# STM32_FYP_DAC_Module.net
KiCad netlist of a schematic drawn in Altium Designer
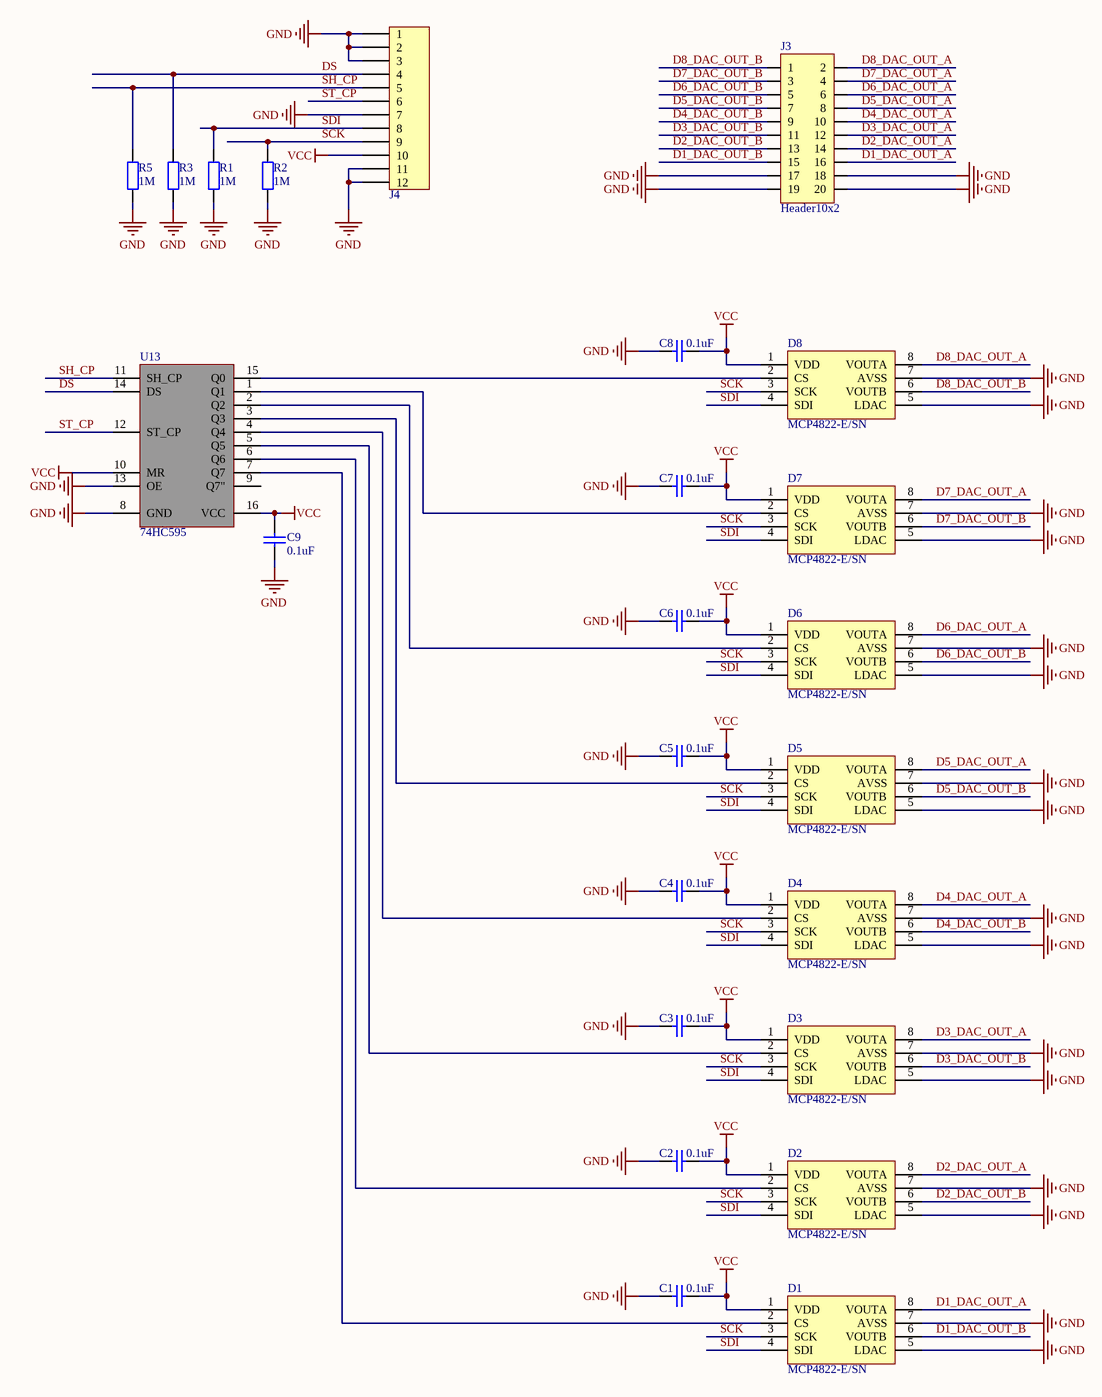
[diagram p0: STM32_FYP_DAC_Module.SchDoc]

(export (version "E")
  (design (tool "Eeschema 10.0.6"))
  (components
    (comp (ref "C1")
      (value "0.1uF")
      (footprint "0805C_M")
      (description "无极性电容")
      (fields (field (name "PUBLISHER") "Altium Limited"))
      (libsource (lib "USER") (part "Cap"))
    )
    (comp (ref "C2")
      (value "0.1uF")
      (footprint "0805C_M")
      (description "无极性电容")
      (fields (field (name "PUBLISHER") "Altium Limited"))
      (libsource (lib "USER") (part "Cap"))
    )
    (comp (ref "C3")
      (value "0.1uF")
      (footprint "0805C_M")
      (description "无极性电容")
      (fields (field (name "PUBLISHER") "Altium Limited"))
      (libsource (lib "USER") (part "Cap"))
    )
    (comp (ref "C4")
      (value "0.1uF")
      (footprint "0805C_M")
      (description "无极性电容")
      (fields (field (name "PUBLISHER") "Altium Limited"))
      (libsource (lib "USER") (part "Cap"))
    )
    (comp (ref "C5")
      (value "0.1uF")
      (footprint "0805C_M")
      (description "无极性电容")
      (fields (field (name "PUBLISHER") "Altium Limited"))
      (libsource (lib "USER") (part "Cap"))
    )
    (comp (ref "C6")
      (value "0.1uF")
      (footprint "0805C_M")
      (description "无极性电容")
      (fields (field (name "PUBLISHER") "Altium Limited"))
      (libsource (lib "USER") (part "Cap"))
    )
    (comp (ref "C7")
      (value "0.1uF")
      (footprint "0805C_M")
      (description "无极性电容")
      (fields (field (name "PUBLISHER") "Altium Limited"))
      (libsource (lib "USER") (part "Cap"))
    )
    (comp (ref "C8")
      (value "0.1uF")
      (footprint "0805C_M")
      (description "无极性电容")
      (fields (field (name "PUBLISHER") "Altium Limited"))
      (libsource (lib "USER") (part "Cap"))
    )
    (comp (ref "C9")
      (value "0.1uF")
      (footprint "0805C_M")
      (description "无极性电容")
      (fields (field (name "PUBLISHER") "Altium Limited"))
      (libsource (lib "USER") (part "Cap"))
    )
    (comp (ref "D1")
      (value "MCP4822-E/SN")
      (footprint "user1:SOIC-8_150mil")
      (description "DAC数模转换芯片")
      (libsource (lib "GUEST") (part "MCP4822"))
    )
    (comp (ref "D2")
      (value "MCP4822-E/SN")
      (footprint "user1:SOIC-8_150mil")
      (description "DAC数模转换芯片")
      (libsource (lib "GUEST") (part "MCP4822"))
    )
    (comp (ref "D3")
      (value "MCP4822-E/SN")
      (footprint "user1:SOIC-8_150mil")
      (description "DAC数模转换芯片")
      (libsource (lib "GUEST") (part "MCP4822"))
    )
    (comp (ref "D4")
      (value "MCP4822-E/SN")
      (footprint "user1:SOIC-8_150mil")
      (description "DAC数模转换芯片")
      (libsource (lib "GUEST") (part "MCP4822"))
    )
    (comp (ref "D5")
      (value "MCP4822-E/SN")
      (footprint "user1:SOIC-8_150mil")
      (description "DAC数模转换芯片")
      (libsource (lib "GUEST") (part "MCP4822"))
    )
    (comp (ref "D6")
      (value "MCP4822-E/SN")
      (footprint "user1:SOIC-8_150mil")
      (description "DAC数模转换芯片")
      (libsource (lib "GUEST") (part "MCP4822"))
    )
    (comp (ref "D7")
      (value "MCP4822-E/SN")
      (footprint "user1:SOIC-8_150mil")
      (description "DAC数模转换芯片")
      (libsource (lib "GUEST") (part "MCP4822"))
    )
    (comp (ref "D8")
      (value "MCP4822-E/SN")
      (footprint "user1:SOIC-8_150mil")
      (description "DAC数模转换芯片")
      (libsource (lib "GUEST") (part "MCP4822"))
    )
    (comp (ref "J3")
      (value "Header10x2")
      (footprint "USER:10PX2-2.54 - H")
      (libsource (lib "USER") (part "Header10x2"))
    )
    (comp (ref "J4")
      (value "Header12")
      (footprint "USER:12P-2.54-H")
      (description "12PIN插座")
      (libsource (lib "USER") (part "Header12"))
    )
    (comp (ref "R1")
      (value "1M")
      (footprint "0805R_M")
      (description "电阻")
      (fields (field (name "PUBLISHER") "Altium Limited"))
      (libsource (lib "USER") (part "Res"))
    )
    (comp (ref "R2")
      (value "1M")
      (footprint "0805R_M")
      (description "电阻")
      (fields (field (name "PUBLISHER") "Altium Limited"))
      (libsource (lib "USER") (part "Res"))
    )
    (comp (ref "R3")
      (value "1M")
      (footprint "0805R_M")
      (description "电阻")
      (fields (field (name "PUBLISHER") "Altium Limited"))
      (libsource (lib "USER") (part "Res"))
    )
    (comp (ref "R5")
      (value "1M")
      (footprint "0805R_M")
      (description "电阻")
      (fields (field (name "PUBLISHER") "Altium Limited"))
      (libsource (lib "USER") (part "Res"))
    )
    (comp (ref "U13")
      (value "74HC595")
      (footprint "user1:SOIC-16_150mil")
      (description "移位寄存器")
      (libsource (lib "GUEST") (part "74LS595"))
    )
  )
  (nets
    (net (code "1") (name "/D1_DAC_OUT_A") (class "Default")
      (node (ref "D1") (pin "8") (pinfunction "VOUTA_8") (pintype "passive"))
      (node (ref "J3") (pin "16") (pinfunction "16_16") (pintype "passive"))
    )
    (net (code "2") (name "/D1_DAC_OUT_B") (class "Default")
      (node (ref "D1") (pin "6") (pinfunction "VOUTB_6") (pintype "passive"))
      (node (ref "J3") (pin "15") (pinfunction "15_15") (pintype "passive"))
    )
    (net (code "3") (name "/D2_DAC_OUT_A") (class "Default")
      (node (ref "D2") (pin "8") (pinfunction "VOUTA_8") (pintype "passive"))
      (node (ref "J3") (pin "14") (pinfunction "14_14") (pintype "passive"))
    )
    (net (code "4") (name "/D2_DAC_OUT_B") (class "Default")
      (node (ref "D2") (pin "6") (pinfunction "VOUTB_6") (pintype "passive"))
      (node (ref "J3") (pin "13") (pinfunction "13_13") (pintype "passive"))
    )
    (net (code "5") (name "/D3_DAC_OUT_A") (class "Default")
      (node (ref "D3") (pin "8") (pinfunction "VOUTA_8") (pintype "passive"))
      (node (ref "J3") (pin "12") (pinfunction "12_12") (pintype "passive"))
    )
    (net (code "6") (name "/D3_DAC_OUT_B") (class "Default")
      (node (ref "D3") (pin "6") (pinfunction "VOUTB_6") (pintype "passive"))
      (node (ref "J3") (pin "11") (pinfunction "11_11") (pintype "passive"))
    )
    (net (code "7") (name "/D4_DAC_OUT_A") (class "Default")
      (node (ref "D4") (pin "8") (pinfunction "VOUTA_8") (pintype "passive"))
      (node (ref "J3") (pin "10") (pinfunction "10_10") (pintype "passive"))
    )
    (net (code "8") (name "/D4_DAC_OUT_B") (class "Default")
      (node (ref "D4") (pin "6") (pinfunction "VOUTB_6") (pintype "passive"))
      (node (ref "J3") (pin "9") (pinfunction "9_9") (pintype "passive"))
    )
    (net (code "9") (name "/D5_DAC_OUT_A") (class "Default")
      (node (ref "D5") (pin "8") (pinfunction "VOUTA_8") (pintype "passive"))
      (node (ref "J3") (pin "8") (pinfunction "8_8") (pintype "passive"))
    )
    (net (code "10") (name "/D5_DAC_OUT_B") (class "Default")
      (node (ref "D5") (pin "6") (pinfunction "VOUTB_6") (pintype "passive"))
      (node (ref "J3") (pin "7") (pinfunction "7_7") (pintype "passive"))
    )
    (net (code "11") (name "/D6_DAC_OUT_A") (class "Default")
      (node (ref "D6") (pin "8") (pinfunction "VOUTA_8") (pintype "passive"))
      (node (ref "J3") (pin "6") (pinfunction "6_6") (pintype "passive"))
    )
    (net (code "12") (name "/D6_DAC_OUT_B") (class "Default")
      (node (ref "D6") (pin "6") (pinfunction "VOUTB_6") (pintype "passive"))
      (node (ref "J3") (pin "5") (pinfunction "5_5") (pintype "passive"))
    )
    (net (code "13") (name "/D7_DAC_OUT_A") (class "Default")
      (node (ref "D7") (pin "8") (pinfunction "VOUTA_8") (pintype "passive"))
      (node (ref "J3") (pin "4") (pinfunction "4_4") (pintype "passive"))
    )
    (net (code "14") (name "/D7_DAC_OUT_B") (class "Default")
      (node (ref "D7") (pin "6") (pinfunction "VOUTB_6") (pintype "passive"))
      (node (ref "J3") (pin "3") (pinfunction "3_3") (pintype "passive"))
    )
    (net (code "15") (name "/D8_DAC_OUT_A") (class "Default")
      (node (ref "D8") (pin "8") (pinfunction "VOUTA_8") (pintype "passive"))
      (node (ref "J3") (pin "2") (pinfunction "2_2") (pintype "passive"))
    )
    (net (code "16") (name "/D8_DAC_OUT_B") (class "Default")
      (node (ref "D8") (pin "6") (pinfunction "VOUTB_6") (pintype "passive"))
      (node (ref "J3") (pin "1") (pinfunction "1_1") (pintype "passive"))
    )
    (net (code "17") (name "/DS") (class "Default")
      (node (ref "J4") (pin "4") (pinfunction "4_4") (pintype "passive"))
      (node (ref "R3") (pin "2") (pinfunction "2_2") (pintype "passive"))
      (node (ref "U13") (pin "14") (pinfunction "DS_14") (pintype "passive"))
    )
    (net (code "18") (name "/SCK") (class "Default")
      (node (ref "D1") (pin "3") (pinfunction "SCK_3") (pintype "passive"))
      (node (ref "D2") (pin "3") (pinfunction "SCK_3") (pintype "passive"))
      (node (ref "D3") (pin "3") (pinfunction "SCK_3") (pintype "passive"))
      (node (ref "D4") (pin "3") (pinfunction "SCK_3") (pintype "passive"))
      (node (ref "D5") (pin "3") (pinfunction "SCK_3") (pintype "passive"))
      (node (ref "D6") (pin "3") (pinfunction "SCK_3") (pintype "passive"))
      (node (ref "D7") (pin "3") (pinfunction "SCK_3") (pintype "passive"))
      (node (ref "D8") (pin "3") (pinfunction "SCK_3") (pintype "passive"))
      (node (ref "J4") (pin "9") (pinfunction "9_9") (pintype "passive"))
      (node (ref "R2") (pin "2") (pinfunction "2_2") (pintype "passive"))
    )
    (net (code "19") (name "/SDI") (class "Default")
      (node (ref "D1") (pin "4") (pinfunction "SDI_4") (pintype "passive"))
      (node (ref "D2") (pin "4") (pinfunction "SDI_4") (pintype "passive"))
      (node (ref "D3") (pin "4") (pinfunction "SDI_4") (pintype "passive"))
      (node (ref "D4") (pin "4") (pinfunction "SDI_4") (pintype "passive"))
      (node (ref "D5") (pin "4") (pinfunction "SDI_4") (pintype "passive"))
      (node (ref "D6") (pin "4") (pinfunction "SDI_4") (pintype "passive"))
      (node (ref "D7") (pin "4") (pinfunction "SDI_4") (pintype "passive"))
      (node (ref "D8") (pin "4") (pinfunction "SDI_4") (pintype "passive"))
      (node (ref "J4") (pin "8") (pinfunction "8_8") (pintype "passive"))
      (node (ref "R1") (pin "2") (pinfunction "2_2") (pintype "passive"))
    )
    (net (code "20") (name "/SH_CP") (class "Default")
      (node (ref "J4") (pin "5") (pinfunction "5_5") (pintype "passive"))
      (node (ref "R5") (pin "2") (pinfunction "2_2") (pintype "passive"))
      (node (ref "U13") (pin "11") (pinfunction "SH_CP_11") (pintype "passive"))
    )
    (net (code "21") (name "/ST_CP") (class "Default")
      (node (ref "J4") (pin "6") (pinfunction "6_6") (pintype "passive"))
      (node (ref "U13") (pin "12") (pinfunction "ST_CP_12") (pintype "passive"))
    )
    (net (code "22") (name "GND") (class "Default")
      (node (ref "C1") (pin "1") (pinfunction "1_1") (pintype "passive"))
      (node (ref "C2") (pin "1") (pinfunction "1_1") (pintype "passive"))
      (node (ref "C3") (pin "1") (pinfunction "1_1") (pintype "passive"))
      (node (ref "C4") (pin "1") (pinfunction "1_1") (pintype "passive"))
      (node (ref "C5") (pin "1") (pinfunction "1_1") (pintype "passive"))
      (node (ref "C6") (pin "1") (pinfunction "1_1") (pintype "passive"))
      (node (ref "C7") (pin "1") (pinfunction "1_1") (pintype "passive"))
      (node (ref "C8") (pin "1") (pinfunction "1_1") (pintype "passive"))
      (node (ref "C9") (pin "1") (pinfunction "1_1") (pintype "passive"))
      (node (ref "D1") (pin "5") (pinfunction "LDAC_5") (pintype "passive"))
      (node (ref "D1") (pin "7") (pinfunction "AVSS_7") (pintype "passive"))
      (node (ref "D2") (pin "5") (pinfunction "LDAC_5") (pintype "passive"))
      (node (ref "D2") (pin "7") (pinfunction "AVSS_7") (pintype "passive"))
      (node (ref "D3") (pin "5") (pinfunction "LDAC_5") (pintype "passive"))
      (node (ref "D3") (pin "7") (pinfunction "AVSS_7") (pintype "passive"))
      (node (ref "D4") (pin "5") (pinfunction "LDAC_5") (pintype "passive"))
      (node (ref "D4") (pin "7") (pinfunction "AVSS_7") (pintype "passive"))
      (node (ref "D5") (pin "5") (pinfunction "LDAC_5") (pintype "passive"))
      (node (ref "D5") (pin "7") (pinfunction "AVSS_7") (pintype "passive"))
      (node (ref "D6") (pin "5") (pinfunction "LDAC_5") (pintype "passive"))
      (node (ref "D6") (pin "7") (pinfunction "AVSS_7") (pintype "passive"))
      (node (ref "D7") (pin "5") (pinfunction "LDAC_5") (pintype "passive"))
      (node (ref "D7") (pin "7") (pinfunction "AVSS_7") (pintype "passive"))
      (node (ref "D8") (pin "5") (pinfunction "LDAC_5") (pintype "passive"))
      (node (ref "D8") (pin "7") (pinfunction "AVSS_7") (pintype "passive"))
      (node (ref "J3") (pin "17") (pinfunction "17_17") (pintype "passive"))
      (node (ref "J3") (pin "18") (pinfunction "18_18") (pintype "passive"))
      (node (ref "J3") (pin "19") (pinfunction "19_19") (pintype "passive"))
      (node (ref "J3") (pin "20") (pinfunction "20_20") (pintype "passive"))
      (node (ref "J4") (pin "1") (pinfunction "1_1") (pintype "passive"))
      (node (ref "J4") (pin "11") (pinfunction "11_11") (pintype "passive"))
      (node (ref "J4") (pin "12") (pinfunction "12_12") (pintype "passive"))
      (node (ref "J4") (pin "2") (pinfunction "2_2") (pintype "passive"))
      (node (ref "J4") (pin "3") (pinfunction "3_3") (pintype "passive"))
      (node (ref "J4") (pin "7") (pinfunction "7_7") (pintype "passive"))
      (node (ref "R1") (pin "1") (pinfunction "1_1") (pintype "passive"))
      (node (ref "R2") (pin "1") (pinfunction "1_1") (pintype "passive"))
      (node (ref "R3") (pin "1") (pinfunction "1_1") (pintype "passive"))
      (node (ref "R5") (pin "1") (pinfunction "1_1") (pintype "passive"))
      (node (ref "U13") (pin "13") (pinfunction "OE_13") (pintype "passive"))
      (node (ref "U13") (pin "8") (pinfunction "GND_8") (pintype "passive"))
    )
    (net (code "23") (name "Net-(D1-CS)") (class "Default")
      (node (ref "D1") (pin "2") (pinfunction "CS_2") (pintype "passive"))
      (node (ref "U13") (pin "7") (pinfunction "Q7_7") (pintype "passive"))
    )
    (net (code "24") (name "Net-(D2-CS)") (class "Default")
      (node (ref "D2") (pin "2") (pinfunction "CS_2") (pintype "passive"))
      (node (ref "U13") (pin "6") (pinfunction "Q6_6") (pintype "passive"))
    )
    (net (code "25") (name "Net-(D3-CS)") (class "Default")
      (node (ref "D3") (pin "2") (pinfunction "CS_2") (pintype "passive"))
      (node (ref "U13") (pin "5") (pinfunction "Q5_5") (pintype "passive"))
    )
    (net (code "26") (name "Net-(D4-CS)") (class "Default")
      (node (ref "D4") (pin "2") (pinfunction "CS_2") (pintype "passive"))
      (node (ref "U13") (pin "4") (pinfunction "Q4_4") (pintype "passive"))
    )
    (net (code "27") (name "Net-(D5-CS)") (class "Default")
      (node (ref "D5") (pin "2") (pinfunction "CS_2") (pintype "passive"))
      (node (ref "U13") (pin "3") (pinfunction "Q3_3") (pintype "passive"))
    )
    (net (code "28") (name "Net-(D6-CS)") (class "Default")
      (node (ref "D6") (pin "2") (pinfunction "CS_2") (pintype "passive"))
      (node (ref "U13") (pin "2") (pinfunction "Q2_2") (pintype "passive"))
    )
    (net (code "29") (name "Net-(D7-CS)") (class "Default")
      (node (ref "D7") (pin "2") (pinfunction "CS_2") (pintype "passive"))
      (node (ref "U13") (pin "1") (pinfunction "Q1_1") (pintype "passive"))
    )
    (net (code "30") (name "Net-(D8-CS)") (class "Default")
      (node (ref "D8") (pin "2") (pinfunction "CS_2") (pintype "passive"))
      (node (ref "U13") (pin "15") (pinfunction "Q0_15") (pintype "passive"))
    )
    (net (code "31") (name "VCC") (class "Default")
      (node (ref "C1") (pin "2") (pinfunction "2_2") (pintype "passive"))
      (node (ref "C2") (pin "2") (pinfunction "2_2") (pintype "passive"))
      (node (ref "C3") (pin "2") (pinfunction "2_2") (pintype "passive"))
      (node (ref "C4") (pin "2") (pinfunction "2_2") (pintype "passive"))
      (node (ref "C5") (pin "2") (pinfunction "2_2") (pintype "passive"))
      (node (ref "C6") (pin "2") (pinfunction "2_2") (pintype "passive"))
      (node (ref "C7") (pin "2") (pinfunction "2_2") (pintype "passive"))
      (node (ref "C8") (pin "2") (pinfunction "2_2") (pintype "passive"))
      (node (ref "C9") (pin "2") (pinfunction "2_2") (pintype "passive"))
      (node (ref "D1") (pin "1") (pinfunction "VDD_1") (pintype "passive"))
      (node (ref "D2") (pin "1") (pinfunction "VDD_1") (pintype "passive"))
      (node (ref "D3") (pin "1") (pinfunction "VDD_1") (pintype "passive"))
      (node (ref "D4") (pin "1") (pinfunction "VDD_1") (pintype "passive"))
      (node (ref "D5") (pin "1") (pinfunction "VDD_1") (pintype "passive"))
      (node (ref "D6") (pin "1") (pinfunction "VDD_1") (pintype "passive"))
      (node (ref "D7") (pin "1") (pinfunction "VDD_1") (pintype "passive"))
      (node (ref "D8") (pin "1") (pinfunction "VDD_1") (pintype "passive"))
      (node (ref "J4") (pin "10") (pinfunction "10_10") (pintype "passive"))
      (node (ref "U13") (pin "10") (pinfunction "MR_10") (pintype "passive"))
      (node (ref "U13") (pin "16") (pinfunction "VCC_16") (pintype "passive"))
    )
    (net (code "32") (name "unconnected-(U13-Q7\"-Pad9)") (class "Default")
      (node (ref "U13") (pin "9") (pinfunction "Q7\"_9") (pintype "passive"))
    )
  )
)
